# flasher_with_opto.net
KiCad netlist of a schematic drawn in EAGLE
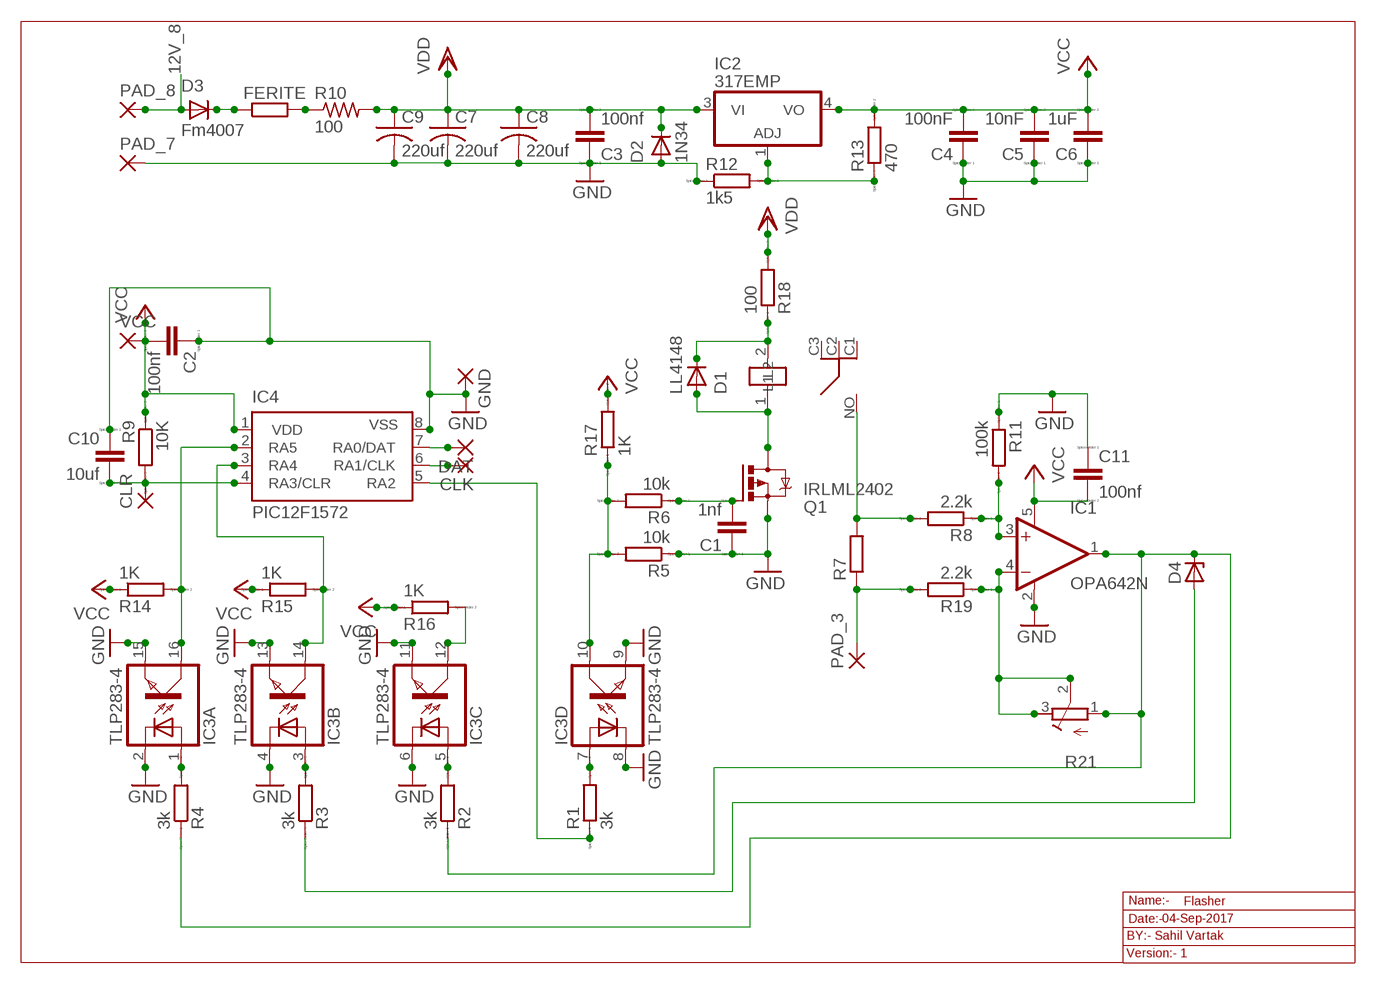
[diagram p0: schematic, sheet 1]

(export (version "E")
  (design (tool "Eeschema 10.0.6"))
  (components
    (comp (ref "C1")
      (value "1nf")
      (footprint "eagle-import:C0603")
      (libsource (lib "eagle-import") (part "CC0603"))
    )
    (comp (ref "C2")
      (value "100nf")
      (footprint "eagle-import:C0603")
      (libsource (lib "eagle-import") (part "CC0603"))
    )
    (comp (ref "C3")
      (value "100nf")
      (footprint "eagle-import:C0603")
      (libsource (lib "eagle-import") (part "CC0603"))
    )
    (comp (ref "C4")
      (value "100nF")
      (footprint "eagle-import:C0603")
      (libsource (lib "eagle-import") (part "CC0603"))
    )
    (comp (ref "C5")
      (value "10nF")
      (footprint "eagle-import:C0603")
      (libsource (lib "eagle-import") (part "CC0603"))
    )
    (comp (ref "C6")
      (value "1uF")
      (footprint "eagle-import:C0603")
      (libsource (lib "eagle-import") (part "CC0603"))
    )
    (comp (ref "C7")
      (value "220uf")
      (footprint "eagle-import:C025-025X050")
      (libsource (lib "eagle-import") (part "C-US025-025X050"))
    )
    (comp (ref "C8")
      (value "220uf")
      (footprint "eagle-import:C025-025X050")
      (libsource (lib "eagle-import") (part "C-US025-025X050"))
    )
    (comp (ref "C9")
      (value "220uf")
      (footprint "eagle-import:C025-025X050")
      (libsource (lib "eagle-import") (part "C-US025-025X050"))
    )
    (comp (ref "C10")
      (value "10uf")
      (footprint "eagle-import:C0603")
      (libsource (lib "eagle-import") (part "CC0603"))
    )
    (comp (ref "C11")
      (value "100nf")
      (footprint "eagle-import:C0603")
      (libsource (lib "eagle-import") (part "CC0603"))
    )
    (comp (ref "CLK")
      (value "1,6/0,8")
      (footprint "eagle-import:1,6_0,8")
      (libsource (lib "eagle-import") (part "1,6/0,8"))
    )
    (comp (ref "CLR")
      (value "1,6/0,8")
      (footprint "eagle-import:1,6_0,8")
      (libsource (lib "eagle-import") (part "1,6/0,8"))
    )
    (comp (ref "D1")
      (value "LL4148")
      (footprint "eagle-import:SMA-DO214AC")
      (libsource (lib "eagle-import") (part "GF1"))
    )
    (comp (ref "D2")
      (value "1N34")
      (footprint "eagle-import:SMA-DO214AC")
      (libsource (lib "eagle-import") (part "GF1"))
    )
    (comp (ref "D3")
      (value "Fm4007")
      (footprint "eagle-import:SMA-DO214AC")
      (libsource (lib "eagle-import") (part "GF1"))
    )
    (comp (ref "D4")
      (value "ZENER-DIODESOD80C")
      (footprint "eagle-import:SOD80C")
      (libsource (lib "eagle-import") (part "ZENER-DIODESOD80C"))
    )
    (comp (ref "DAT")
      (value "1,6/0,8")
      (footprint "eagle-import:1,6_0,8")
      (libsource (lib "eagle-import") (part "1,6/0,8"))
    )
    (comp (ref "FERITE")
      (value "R-EU_R0603")
      (footprint "eagle-import:R0603")
      (libsource (lib "eagle-import") (part "resistor_R-EU_R0603"))
    )
    (comp (ref "GND")
      (value "1,6/0,8")
      (footprint "eagle-import:1,6_0,8")
      (libsource (lib "eagle-import") (part "1,6/0,8"))
    )
    (comp (ref "IC1")
      (value "OPA642N")
      (footprint "eagle-import:SOT23-5")
      (libsource (lib "eagle-import") (part "OPA642N"))
    )
    (comp (ref "IC2")
      (value "317EMP")
      (footprint "eagle-import:SOT223")
      (libsource (lib "eagle-import") (part "317EMP"))
    )
    (comp (ref "IC3")
      (value "TLP283-4")
      (footprint "eagle-import:MINI-FLAT-16")
      (libsource (lib "eagle-import") (part "TLP283-4"))
    )
    (comp (ref "IC4")
      (value "PIC12F1572")
      (footprint "eagle-import:SO-08")
      (fields (field (name "MF") "MICROCHIP") (field (name "MPN") "PIC12F675-E/SN"))
      (libsource (lib "eagle-import") (part "PIC12F6SN75"))
    )
    (comp (ref "K2")
      (value "RL703")
      (footprint "eagle-import:RL703")
      (libsource (lib "eagle-import") (part "RL703"))
    )
    (comp (ref "PAD_3")
      (value "2,54/1,1")
      (footprint "eagle-import:2,54_1,1")
      (libsource (lib "eagle-import") (part "2,54/1,1"))
    )
    (comp (ref "PAD_7")
      (value "2,54/1,1")
      (footprint "eagle-import:2,54_1,1")
      (libsource (lib "eagle-import") (part "2,54/1,1"))
    )
    (comp (ref "PAD_8")
      (value "2,54/1,1")
      (footprint "eagle-import:2,54_1,1")
      (libsource (lib "eagle-import") (part "2,54/1,1"))
    )
    (comp (ref "Q1")
      (value "IRLML2402")
      (footprint "eagle-import:MICRO3")
      (libsource (lib "eagle-import") (part "IRLML5203"))
    )
    (comp (ref "R1")
      (value "3k")
      (footprint "eagle-import:R0603")
      (libsource (lib "eagle-import") (part "RR0603"))
    )
    (comp (ref "R2")
      (value "3k")
      (footprint "eagle-import:R0603")
      (libsource (lib "eagle-import") (part "RR0603"))
    )
    (comp (ref "R3")
      (value "3k")
      (footprint "eagle-import:R0603")
      (libsource (lib "eagle-import") (part "RR0603"))
    )
    (comp (ref "R4")
      (value "3k")
      (footprint "eagle-import:R0603")
      (libsource (lib "eagle-import") (part "RR0603"))
    )
    (comp (ref "R5")
      (value "10k")
      (footprint "eagle-import:R0603")
      (libsource (lib "eagle-import") (part "RR0603"))
    )
    (comp (ref "R6")
      (value "10k")
      (footprint "eagle-import:R0603")
      (libsource (lib "eagle-import") (part "RR0603"))
    )
    (comp (ref "R7")
      (value "R-EU_VTA54")
      (footprint "eagle-import:VTA54")
      (libsource (lib "eagle-import") (part "R-EU_VTA54"))
    )
    (comp (ref "R8")
      (value "2.2k")
      (footprint "eagle-import:R0603")
      (libsource (lib "eagle-import") (part "RR0603"))
    )
    (comp (ref "R9")
      (value "10K")
      (footprint "eagle-import:R0603")
      (libsource (lib "eagle-import") (part "RR0603"))
    )
    (comp (ref "R10")
      (value "100")
      (footprint "eagle-import:WSC2515")
      (libsource (lib "eagle-import") (part "R-US_WSC2515"))
    )
    (comp (ref "R11")
      (value "100k")
      (footprint "eagle-import:R0603")
      (libsource (lib "eagle-import") (part "RR0603"))
    )
    (comp (ref "R12")
      (value "1k5")
      (footprint "eagle-import:R0603")
      (libsource (lib "eagle-import") (part "RR0603"))
    )
    (comp (ref "R13")
      (value "470")
      (footprint "eagle-import:R0603")
      (libsource (lib "eagle-import") (part "RR0603"))
    )
    (comp (ref "R14")
      (value "1K")
      (footprint "eagle-import:R0603")
      (libsource (lib "eagle-import") (part "RR0603"))
    )
    (comp (ref "R15")
      (value "1K")
      (footprint "eagle-import:R0603")
      (libsource (lib "eagle-import") (part "RR0603"))
    )
    (comp (ref "R16")
      (value "1K")
      (footprint "eagle-import:R0603")
      (libsource (lib "eagle-import") (part "RR0603"))
    )
    (comp (ref "R17")
      (value "1K")
      (footprint "eagle-import:R0603")
      (libsource (lib "eagle-import") (part "RR0603"))
    )
    (comp (ref "R18")
      (value "100")
      (footprint "eagle-import:R0603")
      (libsource (lib "eagle-import") (part "RR0603"))
    )
    (comp (ref "R19")
      (value "2.2k")
      (footprint "eagle-import:R0603")
      (libsource (lib "eagle-import") (part "RR0603"))
    )
    (comp (ref "R21")
      (value "R-TRIMMTS63X")
      (footprint "eagle-import:RTRIMTS63X")
      (libsource (lib "eagle-import") (part "R-TRIMMTS63X"))
    )
    (comp (ref "VCC")
      (value "1,6/0,8")
      (footprint "eagle-import:1,6_0,8")
      (libsource (lib "eagle-import") (part "1,6/0,8"))
    )
  )
  (nets
    (net (code "1") (name "/12V_8") (class "Default")
      (node (ref "D3") (pin "A") (pinfunction "A_A") (pintype "passive"))
      (node (ref "PAD_8") (pin "1") (pinfunction "P_1") (pintype "passive"))
    )
    (net (code "2") (name "GND") (class "Default")
      (node (ref "C1") (pin "1") (pinfunction "1_1") (pintype "passive"))
      (node (ref "C10") (pin "1") (pinfunction "1_1") (pintype "passive"))
      (node (ref "C11") (pin "1") (pinfunction "1_1") (pintype "passive"))
      (node (ref "C2") (pin "1") (pinfunction "1_1") (pintype "passive"))
      (node (ref "C3") (pin "1") (pinfunction "1_1") (pintype "passive"))
      (node (ref "C4") (pin "1") (pinfunction "1_1") (pintype "passive"))
      (node (ref "C5") (pin "1") (pinfunction "1_1") (pintype "passive"))
      (node (ref "C6") (pin "1") (pinfunction "1_1") (pintype "passive"))
      (node (ref "C7") (pin "2") (pinfunction "2_2") (pintype "passive"))
      (node (ref "C8") (pin "2") (pinfunction "2_2") (pintype "passive"))
      (node (ref "C9") (pin "2") (pinfunction "2_2") (pintype "passive"))
      (node (ref "D2") (pin "A") (pinfunction "A_A") (pintype "passive"))
      (node (ref "GND") (pin "1") (pinfunction "P_1") (pintype "passive"))
      (node (ref "IC1") (pin "2") (pinfunction "V-_2") (pintype "power_in"))
      (node (ref "IC3") (pin "11") (pinfunction "EMIT_11") (pintype "passive"))
      (node (ref "IC3") (pin "13") (pinfunction "EMIT_13") (pintype "passive"))
      (node (ref "IC3") (pin "15") (pinfunction "EMIT_15") (pintype "passive"))
      (node (ref "IC3") (pin "2") (pinfunction "C_2") (pintype "passive"))
      (node (ref "IC3") (pin "4") (pinfunction "C_4") (pintype "passive"))
      (node (ref "IC3") (pin "6") (pinfunction "C_6") (pintype "passive"))
      (node (ref "IC3") (pin "8") (pinfunction "C_8") (pintype "passive"))
      (node (ref "IC3") (pin "9") (pinfunction "EMIT_9") (pintype "passive"))
      (node (ref "IC4") (pin "8") (pinfunction "VSS_8") (pintype "power_in"))
      (node (ref "PAD_7") (pin "1") (pinfunction "P_1") (pintype "passive"))
      (node (ref "Q1") (pin "2") (pinfunction "S_2") (pintype "passive"))
      (node (ref "R11") (pin "1") (pinfunction "1_1") (pintype "passive"))
      (node (ref "R12") (pin "1") (pinfunction "1_1") (pintype "passive"))
      (node (ref "R5") (pin "1") (pinfunction "1_1") (pintype "passive"))
    )
    (net (code "3") (name "Net-(CLK-P)") (class "Default")
      (node (ref "CLK") (pin "1") (pinfunction "P_1") (pintype "passive"))
      (node (ref "IC4") (pin "6") (pinfunction "RA1/CLK_6") (pintype "bidirectional"))
    )
    (net (code "4") (name "Net-(CLR-P)") (class "Default")
      (node (ref "C10") (pin "2") (pinfunction "2_2") (pintype "passive"))
      (node (ref "CLR") (pin "1") (pinfunction "P_1") (pintype "passive"))
      (node (ref "IC4") (pin "4") (pinfunction "RA3/CLR_4") (pintype "input"))
      (node (ref "R9") (pin "2") (pinfunction "2_2") (pintype "passive"))
    )
    (net (code "5") (name "Net-(D1-C)") (class "Default")
      (node (ref "D1") (pin "K") (pinfunction "C_K") (pintype "passive"))
      (node (ref "K2") (pin "2") (pinfunction "L1_2") (pintype "bidirectional"))
      (node (ref "R18") (pin "1") (pinfunction "1_1") (pintype "passive"))
    )
    (net (code "6") (name "Net-(D3-C)") (class "Default")
      (node (ref "D3") (pin "K") (pinfunction "C_K") (pintype "passive"))
      (node (ref "FERITE") (pin "1") (pinfunction "1_1") (pintype "passive"))
    )
    (net (code "7") (name "Net-(D4-PadA)") (class "Default")
      (node (ref "D4") (pin "A") (pinfunction "A_A") (pintype "passive"))
      (node (ref "R3") (pin "1") (pinfunction "1_1") (pintype "passive"))
    )
    (net (code "8") (name "Net-(DAT-P)") (class "Default")
      (node (ref "DAT") (pin "1") (pinfunction "P_1") (pintype "passive"))
      (node (ref "IC4") (pin "7") (pinfunction "RA0/DAT_7") (pintype "bidirectional"))
    )
    (net (code "9") (name "Net-(FERITE-Pad2)") (class "Default")
      (node (ref "FERITE") (pin "2") (pinfunction "2_2") (pintype "passive"))
      (node (ref "R10") (pin "1") (pinfunction "1_1") (pintype "passive"))
    )
    (net (code "10") (name "Net-(IC1-+IN)") (class "Default")
      (node (ref "IC1") (pin "3") (pinfunction "+IN_3") (pintype "input"))
      (node (ref "R11") (pin "2") (pinfunction "2_2") (pintype "passive"))
      (node (ref "R8") (pin "1") (pinfunction "1_1") (pintype "passive"))
    )
    (net (code "11") (name "Net-(IC1--IN)") (class "Default")
      (node (ref "IC1") (pin "4") (pinfunction "-IN_4") (pintype "input"))
      (node (ref "R19") (pin "1") (pinfunction "1_1") (pintype "passive"))
      (node (ref "R21") (pin "2") (pinfunction "S_2") (pintype "passive"))
      (node (ref "R21") (pin "3") (pinfunction "E_3") (pintype "passive"))
    )
    (net (code "12") (name "Net-(IC1-OUT)") (class "Default")
      (node (ref "D4") (pin "C") (pinfunction "C_C") (pintype "passive"))
      (node (ref "IC1") (pin "1") (pinfunction "OUT_1") (pintype "output"))
      (node (ref "R2") (pin "1") (pinfunction "1_1") (pintype "passive"))
      (node (ref "R21") (pin "1") (pinfunction "A_1") (pintype "passive"))
      (node (ref "R4") (pin "1") (pinfunction "1_1") (pintype "passive"))
    )
    (net (code "13") (name "Net-(IC2-ADJ)") (class "Default")
      (node (ref "IC2") (pin "1") (pinfunction "ADJ_1") (pintype "input"))
      (node (ref "R12") (pin "2") (pinfunction "2_2") (pintype "passive"))
      (node (ref "R13") (pin "1") (pinfunction "1_1") (pintype "passive"))
    )
    (net (code "14") (name "Net-(IC3A-A)") (class "Default")
      (node (ref "IC3") (pin "1") (pinfunction "A_1") (pintype "passive"))
      (node (ref "R4") (pin "2") (pinfunction "2_2") (pintype "passive"))
    )
    (net (code "15") (name "Net-(IC3A-COL)") (class "Default")
      (node (ref "IC3") (pin "16") (pinfunction "COL_16") (pintype "passive"))
      (node (ref "IC4") (pin "2") (pinfunction "RA5_2") (pintype "bidirectional"))
      (node (ref "R14") (pin "2") (pinfunction "2_2") (pintype "passive"))
    )
    (net (code "16") (name "Net-(IC3B-A)") (class "Default")
      (node (ref "IC3") (pin "3") (pinfunction "A_3") (pintype "passive"))
      (node (ref "R3") (pin "2") (pinfunction "2_2") (pintype "passive"))
    )
    (net (code "17") (name "Net-(IC3B-COL)") (class "Default")
      (node (ref "IC3") (pin "14") (pinfunction "COL_14") (pintype "passive"))
      (node (ref "IC4") (pin "3") (pinfunction "RA4_3") (pintype "bidirectional"))
      (node (ref "R15") (pin "2") (pinfunction "2_2") (pintype "passive"))
    )
    (net (code "18") (name "Net-(IC3C-A)") (class "Default")
      (node (ref "IC3") (pin "5") (pinfunction "A_5") (pintype "passive"))
      (node (ref "R2") (pin "2") (pinfunction "2_2") (pintype "passive"))
    )
    (net (code "19") (name "Net-(IC3C-COL)") (class "Default")
      (node (ref "IC3") (pin "12") (pinfunction "COL_12") (pintype "passive"))
      (node (ref "R16") (pin "2") (pinfunction "2_2") (pintype "passive"))
    )
    (net (code "20") (name "Net-(IC3D-A)") (class "Default")
      (node (ref "IC3") (pin "7") (pinfunction "A_7") (pintype "passive"))
      (node (ref "R1") (pin "2") (pinfunction "2_2") (pintype "passive"))
    )
    (net (code "21") (name "Net-(IC3D-COL)") (class "Default")
      (node (ref "IC3") (pin "10") (pinfunction "COL_10") (pintype "passive"))
      (node (ref "R17") (pin "1") (pinfunction "1_1") (pintype "passive"))
      (node (ref "R5") (pin "2") (pinfunction "2_2") (pintype "passive"))
      (node (ref "R6") (pin "2") (pinfunction "2_2") (pintype "passive"))
    )
    (net (code "22") (name "Net-(IC4-RA2)") (class "Default")
      (node (ref "IC4") (pin "5") (pinfunction "RA2_5") (pintype "bidirectional"))
      (node (ref "R1") (pin "1") (pinfunction "1_1") (pintype "passive"))
    )
    (net (code "23") (name "Net-(K2-L2)") (class "Default")
      (node (ref "D1") (pin "A") (pinfunction "A_A") (pintype "passive"))
      (node (ref "K2") (pin "1") (pinfunction "L2_1") (pintype "bidirectional"))
      (node (ref "Q1") (pin "3") (pinfunction "D_3") (pintype "passive"))
    )
    (net (code "24") (name "Net-(K2-PadNO)") (class "Default")
      (node (ref "K2") (pin "NO") (pinfunction "NO_NO") (pintype "bidirectional"))
      (node (ref "R7") (pin "2") (pinfunction "2_2") (pintype "passive"))
      (node (ref "R8") (pin "2") (pinfunction "2_2") (pintype "passive"))
    )
    (net (code "25") (name "Net-(PAD_3-P)") (class "Default")
      (node (ref "PAD_3") (pin "1") (pinfunction "P_1") (pintype "passive"))
      (node (ref "R19") (pin "2") (pinfunction "2_2") (pintype "passive"))
      (node (ref "R7") (pin "1") (pinfunction "1_1") (pintype "passive"))
    )
    (net (code "26") (name "Net-(Q1-G)") (class "Default")
      (node (ref "C1") (pin "2") (pinfunction "2_2") (pintype "passive"))
      (node (ref "Q1") (pin "1") (pinfunction "G_1") (pintype "passive"))
      (node (ref "R6") (pin "1") (pinfunction "1_1") (pintype "passive"))
    )
    (net (code "27") (name "VCC") (class "Default")
      (node (ref "C11") (pin "2") (pinfunction "2_2") (pintype "passive"))
      (node (ref "C2") (pin "2") (pinfunction "2_2") (pintype "passive"))
      (node (ref "C4") (pin "2") (pinfunction "2_2") (pintype "passive"))
      (node (ref "C5") (pin "2") (pinfunction "2_2") (pintype "passive"))
      (node (ref "C6") (pin "2") (pinfunction "2_2") (pintype "passive"))
      (node (ref "IC1") (pin "5") (pinfunction "V+_5") (pintype "power_in"))
      (node (ref "IC2") (pin "4") (pinfunction "VO_4") (pintype "passive"))
      (node (ref "IC4") (pin "1") (pinfunction "VDD_1") (pintype "power_in"))
      (node (ref "R13") (pin "2") (pinfunction "2_2") (pintype "passive"))
      (node (ref "R14") (pin "1") (pinfunction "1_1") (pintype "passive"))
      (node (ref "R15") (pin "1") (pinfunction "1_1") (pintype "passive"))
      (node (ref "R16") (pin "1") (pinfunction "1_1") (pintype "passive"))
      (node (ref "R17") (pin "2") (pinfunction "2_2") (pintype "passive"))
      (node (ref "R9") (pin "1") (pinfunction "1_1") (pintype "passive"))
      (node (ref "VCC") (pin "1") (pinfunction "P_1") (pintype "passive"))
    )
    (net (code "28") (name "VDD") (class "Default")
      (node (ref "C3") (pin "2") (pinfunction "2_2") (pintype "passive"))
      (node (ref "C7") (pin "1") (pinfunction "1_1") (pintype "passive"))
      (node (ref "C8") (pin "1") (pinfunction "1_1") (pintype "passive"))
      (node (ref "C9") (pin "1") (pinfunction "1_1") (pintype "passive"))
      (node (ref "D2") (pin "K") (pinfunction "C_K") (pintype "passive"))
      (node (ref "IC2") (pin "3") (pinfunction "VI_3") (pintype "input"))
      (node (ref "R10") (pin "2") (pinfunction "2_2") (pintype "passive"))
      (node (ref "R18") (pin "2") (pinfunction "2_2") (pintype "passive"))
    )
    (net (code "29") (name "unconnected-(K2-PadC1)") (class "Default")
      (node (ref "K2") (pin "C1") (pinfunction "C1_C1") (pintype "bidirectional"))
    )
    (net (code "30") (name "unconnected-(K2-PadC2)") (class "Default")
      (node (ref "K2") (pin "C2") (pinfunction "C2_C2") (pintype "bidirectional"))
    )
    (net (code "31") (name "unconnected-(K2-PadC3)") (class "Default")
      (node (ref "K2") (pin "C3") (pinfunction "C3_C3") (pintype "bidirectional"))
    )
  )
)
